# Controller.net
KiCad netlist of a schematic drawn in Altium Designer
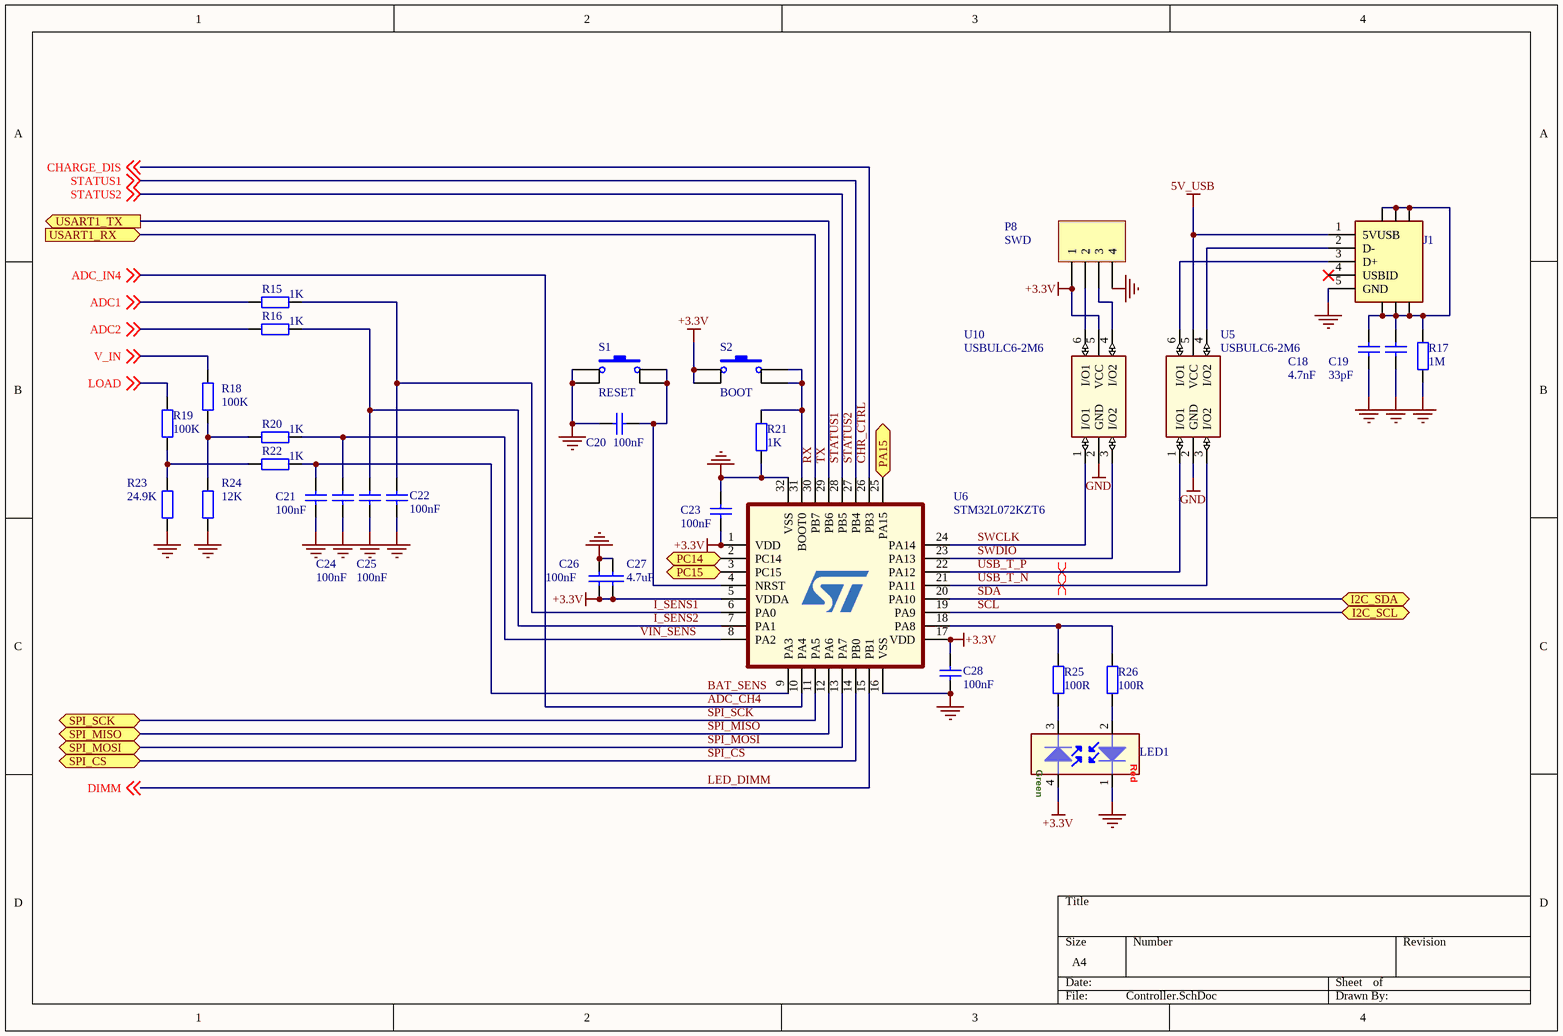
[diagram p0: Controller.SchDoc]

(export (version "E")
  (design (tool "Eeschema 10.0.6"))
  (components
    (comp (ref "C18")
      (value "4.7nF")
      (footprint "C0402")
      (description "Capacitor ceramic")
      (fields
        (field (name "MANUFACTURER") "Yageo")
        (field (name "MANUFACTURER PART NO.") "AC0402KRX7R9BB472")
      )
      (libsource (lib "Miscellaneous Devices") (part "Cap Semi"))
    )
    (comp (ref "C19")
      (value "33pF")
      (footprint "C0402")
      (description "Capacitor ceramic")
      (fields
        (field (name "MANUFACTURER") "Yageo")
        (field (name "MANUFACTURER PART NO.") "CC0402JRNPO9BN330")
      )
      (libsource (lib "Miscellaneous Devices") (part "Cap Semi"))
    )
    (comp (ref "C20")
      (value "100nF")
      (footprint "C0402")
      (description "Capacitor ceramic")
      (fields
        (field (name "MANUFACTURER") "TDK Corporation")
        (field (name "MANUFACTURER PART NO.") "CGA2B3X7R1V104K050BB")
      )
      (libsource (lib "Miscellaneous Devices") (part "Cap Semi"))
    )
    (comp (ref "C21")
      (value "100nF")
      (footprint "C0402")
      (description "Capacitor ceramic")
      (fields
        (field (name "MANUFACTURER") "TDK Corporation")
        (field (name "MANUFACTURER PART NO.") "CGA2B3X7R1V104K050BB")
      )
      (libsource (lib "Miscellaneous Devices") (part "Cap"))
    )
    (comp (ref "C22")
      (value "100nF")
      (footprint "C0402")
      (description "Capacitor ceramic")
      (fields
        (field (name "MANUFACTURER") "TDK Corporation")
        (field (name "MANUFACTURER PART NO.") "CGA2B3X7R1V104K050BB")
      )
      (libsource (lib "Miscellaneous Devices") (part "Cap"))
    )
    (comp (ref "C23")
      (value "100nF")
      (footprint "C0402")
      (description "Capacitor ceramic")
      (fields
        (field (name "MANUFACTURER") "TDK Corporation")
        (field (name "MANUFACTURER PART NO.") "CGA2B3X7R1V104K050BB")
      )
      (libsource (lib "Miscellaneous Devices") (part "Cap"))
    )
    (comp (ref "C24")
      (value "100nF")
      (footprint "C0402")
      (description "Capacitor ceramic")
      (fields
        (field (name "MANUFACTURER") "TDK Corporation")
        (field (name "MANUFACTURER PART NO.") "CGA2B3X7R1V104K050BB")
      )
      (libsource (lib "Miscellaneous Devices") (part "Cap"))
    )
    (comp (ref "C25")
      (value "100nF")
      (footprint "C0402")
      (description "Capacitor ceramic")
      (fields
        (field (name "MANUFACTURER") "TDK Corporation")
        (field (name "MANUFACTURER PART NO.") "CGA2B3X7R1V104K050BB")
      )
      (libsource (lib "Miscellaneous Devices") (part "Cap"))
    )
    (comp (ref "C26")
      (value "100nF")
      (footprint "C0402")
      (description "Capacitor ceramic")
      (fields
        (field (name "MANUFACTURER") "TDK Corporation")
        (field (name "MANUFACTURER PART NO.") "CGA2B3X7R1V104K050BB")
      )
      (libsource (lib "Miscellaneous Devices") (part "Cap"))
    )
    (comp (ref "C27")
      (value "4.7uF")
      (footprint "C0805")
      (description "Capacitor ceramic")
      (fields
        (field (name "MANUFACTURER") "Murata Electronics")
        (field (name "MANUFACTURER PART NO.") "GRM219R6YA475KA73D")
      )
      (libsource (lib "Miscellaneous Devices") (part "Cap Semi"))
    )
    (comp (ref "C28")
      (value "100nF")
      (footprint "C0402")
      (description "Capacitor ceramic")
      (fields
        (field (name "MANUFACTURER") "TDK Corporation")
        (field (name "MANUFACTURER PART NO.") "CGA2B3X7R1V104K050BB")
      )
      (libsource (lib "Miscellaneous Devices") (part "Cap"))
    )
    (comp (ref "J1")
      (value "CON-000116-01")
      (footprint "10118192-0001LF")
      (fields
        (field (name "MANUFACTURER") "Amphenol ICC (FCI)")
        (field (name "MANUFACTURER PART NO.") "10118192-0001LF")
      )
      (libsource (lib "MPPT_Charger_NB_IoT") (part "CON-000116-01"))
    )
    (comp (ref "LED1")
      (value "LED_BICOLOR")
      (footprint "PLCC-4")
      (fields
        (field (name "MANUFACTURER") "OSRAM Opto Semiconductors Inc.")
        (field (name "MANUFACTURER PART NO.") "LSG T67K-JL-1+HK-1")
      )
      (libsource (lib "LED_BiColor") (part "LED_BICOLOR"))
    )
    (comp (ref "P8")
      (value "SWD")
      (footprint "HDR1X4")
      (description "Header, 4-Pin")
      (fields
        (field (name "MANUFACTURER") "Samtec Inc.")
        (field (name "MANUFACTURER PART NO.") "SLW-104-01-G-S")
      )
      (libsource (lib "Miscellaneous Connectors") (part "Header 4"))
    )
    (comp (ref "R15")
      (value "1K")
      (footprint "R0402")
      (description "Resistor")
      (fields (field (name "MANUFACTURER") "Yageo") (field (name "MANUFACTURER PART NO.") "AC0402JR-071KL"))
      (libsource (lib "") (part "Res2_2"))
    )
    (comp (ref "R16")
      (value "1K")
      (footprint "R0402")
      (description "Resistor")
      (fields (field (name "MANUFACTURER") "Yageo") (field (name "MANUFACTURER PART NO.") "AC0402JR-071KL"))
      (libsource (lib "") (part "Res2_2"))
    )
    (comp (ref "R17")
      (value "1M")
      (footprint "R0402")
      (description "Resistor")
      (fields (field (name "MANUFACTURER") "Yageo") (field (name "MANUFACTURER PART NO.") "RC0402FR-071ML"))
      (libsource (lib "") (part "Res2_1"))
    )
    (comp (ref "R18")
      (value "100K")
      (footprint "R0402")
      (description "Resistor")
      (fields (field (name "MANUFACTURER") "Yageo") (field (name "MANUFACTURER PART NO.") "RC0402JR-07100KL"))
      (libsource (lib "") (part "Res2_1"))
    )
    (comp (ref "R19")
      (value "100K")
      (footprint "R0402")
      (description "Resistor")
      (fields (field (name "MANUFACTURER") "Yageo") (field (name "MANUFACTURER PART NO.") "RC0402JR-07100KL"))
      (libsource (lib "Miscellaneous Devices") (part "Res2"))
    )
    (comp (ref "R20")
      (value "1K")
      (footprint "R0402")
      (description "Resistor")
      (fields (field (name "MANUFACTURER") "Yageo") (field (name "MANUFACTURER PART NO.") "AC0402JR-071KL"))
      (libsource (lib "") (part "Res2_2"))
    )
    (comp (ref "R21")
      (value "1K")
      (footprint "R0402")
      (description "Resistor")
      (fields (field (name "MANUFACTURER") "Yageo") (field (name "MANUFACTURER PART NO.") "AC0402JR-071KL"))
      (libsource (lib "") (part "Res2_1"))
    )
    (comp (ref "R22")
      (value "1K")
      (footprint "R0402")
      (description "Resistor")
      (fields (field (name "MANUFACTURER") "Yageo") (field (name "MANUFACTURER PART NO.") "AC0402JR-071KL"))
      (libsource (lib "") (part "Res2_2"))
    )
    (comp (ref "R23")
      (value "24.9K")
      (footprint "R0402")
      (description "Resistor")
      (fields (field (name "MANUFACTURER") "Yageo") (field (name "MANUFACTURER PART NO.") "RC0402FR-0724K9L"))
      (libsource (lib "Miscellaneous Devices") (part "Res2"))
    )
    (comp (ref "R24")
      (value "12K")
      (footprint "R0402")
      (description "Resistor")
      (fields (field (name "MANUFACTURER") "Yageo") (field (name "MANUFACTURER PART NO.") "RC0402JR-0712KL"))
      (libsource (lib "") (part "Res2_1"))
    )
    (comp (ref "R25")
      (value "100R")
      (footprint "R0402")
      (description "Resistor")
      (fields (field (name "MANUFACTURER") "Yageo") (field (name "MANUFACTURER PART NO.") "SR0402JR-7W100RL"))
      (libsource (lib "Miscellaneous Devices") (part "Res2"))
    )
    (comp (ref "R26")
      (value "100R")
      (footprint "R0402")
      (description "Resistor")
      (fields (field (name "MANUFACTURER") "Yageo") (field (name "MANUFACTURER PART NO.") "SR0402JR-7W100RL"))
      (libsource (lib "Miscellaneous Devices") (part "Res2"))
    )
    (comp (ref "S1")
      (value "RESET")
      (footprint "EVQPUA")
      (description "Switch")
      (fields (field (name "MANUFACTURER") "Panasonic") (field (name "MANUFACTURER PART NO.") "EVQPUJ02K"))
      (libsource (lib "RUT_GE310_GNSS") (part "SW-PB"))
    )
    (comp (ref "S2")
      (value "BOOT")
      (footprint "EVQPUA")
      (description "Switch")
      (fields (field (name "MANUFACTURER") "Panasonic") (field (name "MANUFACTURER PART NO.") "EVQPUJ02K"))
      (libsource (lib "RUT_GE310_GNSS") (part "SW-PB"))
    )
    (comp (ref "U5")
      (value "USBULC6-2M6")
      (footprint "Micro_QFN_6L")
      (description "Ultra large bandwidth ESD protection")
      (fields (field (name "MANUFACTURER") "STMicroelectronics"))
      (libsource (lib "USBULC6-2M6") (part "USBULC6-2M6"))
    )
    (comp (ref "U6")
      (value "STM32L072KZT6")
      (footprint "LQFP32")
      (description "Ultra-low-power 32-bit MCU Arm®-based Cortex®-M0+")
      (fields (field (name "MANUFACTURER") "STMicroelectronics"))
      (libsource (lib "STM32L072KZT6") (part "STM32L072KZT6"))
    )
    (comp (ref "U10")
      (value "USBULC6-2M6")
      (footprint "Micro_QFN_6L")
      (description "Ultra large bandwidth ESD protection")
      (fields (field (name "MANUFACTURER") "STMicroelectronics"))
      (libsource (lib "USBULC6-2M6") (part "USBULC6-2M6"))
    )
  )
  (nets
    (net (code "1") (name "+3.3V") (class "Default")
      (node (ref "C23") (pin "2") (pinfunction "2_2") (pintype "passive"))
      (node (ref "C26") (pin "2") (pinfunction "2_2") (pintype "passive"))
      (node (ref "C27") (pin "1") (pinfunction "1_1") (pintype "passive"))
      (node (ref "C28") (pin "1") (pinfunction "1_1") (pintype "passive"))
      (node (ref "LED1") (pin "4") (pinfunction "4_4") (pintype "passive"))
      (node (ref "P8") (pin "1") (pinfunction "1_1") (pintype "passive"))
      (node (ref "S2") (pin "1") (pinfunction "1_1") (pintype "passive"))
      (node (ref "S2") (pin "3") (pinfunction "3_3") (pintype "passive"))
      (node (ref "U10") (pin "5") (pinfunction "VCC_5") (pintype "power_in"))
      (node (ref "U6") (pin "1") (pinfunction "VDD_1") (pintype "passive"))
      (node (ref "U6") (pin "17") (pinfunction "VDD_17") (pintype "passive"))
      (node (ref "U6") (pin "5") (pinfunction "VDDA_5") (pintype "passive"))
    )
    (net (code "2") (name "/BAT_SENS") (class "Default")
      (node (ref "C21") (pin "1") (pinfunction "1_1") (pintype "passive"))
      (node (ref "R22") (pin "2") (pinfunction "2_2") (pintype "passive"))
      (node (ref "U6") (pin "9") (pinfunction "PA3_9") (pintype "passive"))
    )
    (net (code "3") (name "/I_SENS1") (class "Default")
      (node (ref "C22") (pin "1") (pinfunction "1_1") (pintype "passive"))
      (node (ref "R15") (pin "2") (pinfunction "2_2") (pintype "passive"))
      (node (ref "U6") (pin "6") (pinfunction "PA0_6") (pintype "passive"))
    )
    (net (code "4") (name "/I_SENS2") (class "Default")
      (node (ref "C25") (pin "1") (pinfunction "1_1") (pintype "passive"))
      (node (ref "R16") (pin "2") (pinfunction "2_2") (pintype "passive"))
      (node (ref "U6") (pin "7") (pinfunction "PA1_7") (pintype "passive"))
    )
    (net (code "5") (name "/PA15") (class "Default")
      (node (ref "U6") (pin "25") (pinfunction "PA15_25") (pintype "passive"))
    )
    (net (code "6") (name "/PC14") (class "Default")
      (node (ref "U6") (pin "2") (pinfunction "PC14_2") (pintype "passive"))
    )
    (net (code "7") (name "/PC15") (class "Default")
      (node (ref "U6") (pin "3") (pinfunction "PC15_3") (pintype "passive"))
    )
    (net (code "8") (name "/RX") (class "Default")
      (node (ref "U6") (pin "30") (pinfunction "PB7_30") (pintype "passive"))
    )
    (net (code "9") (name "/SCL") (class "Default")
      (node (ref "U6") (pin "19") (pinfunction "PA9_19") (pintype "passive"))
    )
    (net (code "10") (name "/SDA") (class "Default")
      (node (ref "U6") (pin "20") (pinfunction "PA10_20") (pintype "passive"))
    )
    (net (code "11") (name "/SPI_CS") (class "Default")
      (node (ref "U6") (pin "14") (pinfunction "PB0_14") (pintype "passive"))
    )
    (net (code "12") (name "/SPI_MISO") (class "Default")
      (node (ref "U6") (pin "12") (pinfunction "PA6_12") (pintype "passive"))
    )
    (net (code "13") (name "/SPI_MOSI") (class "Default")
      (node (ref "U6") (pin "13") (pinfunction "PA7_13") (pintype "passive"))
    )
    (net (code "14") (name "/SPI_SCK") (class "Default")
      (node (ref "U6") (pin "11") (pinfunction "PA5_11") (pintype "passive"))
    )
    (net (code "15") (name "/SWCLK") (class "Default")
      (node (ref "U10") (pin "1") (pinfunction "I/O1_1") (pintype "bidirectional"))
      (node (ref "U6") (pin "24") (pinfunction "PA14_24") (pintype "passive"))
    )
    (net (code "16") (name "/SWDIO") (class "Default")
      (node (ref "U10") (pin "3") (pinfunction "I/O2_3") (pintype "bidirectional"))
      (node (ref "U6") (pin "23") (pinfunction "PA13_23") (pintype "passive"))
    )
    (net (code "17") (name "/TX") (class "Default")
      (node (ref "U6") (pin "29") (pinfunction "PB6_29") (pintype "passive"))
    )
    (net (code "18") (name "/USB_T_N") (class "Default")
      (node (ref "U5") (pin "3") (pinfunction "I/O2_3") (pintype "bidirectional"))
      (node (ref "U6") (pin "21") (pinfunction "PA11_21") (pintype "passive"))
    )
    (net (code "19") (name "/USB_T_P") (class "Default")
      (node (ref "U5") (pin "1") (pinfunction "I/O1_1") (pintype "bidirectional"))
      (node (ref "U6") (pin "22") (pinfunction "PA12_22") (pintype "passive"))
    )
    (net (code "20") (name "/VIN_SENS") (class "Default")
      (node (ref "C24") (pin "1") (pinfunction "1_1") (pintype "passive"))
      (node (ref "R20") (pin "2") (pinfunction "2_2") (pintype "passive"))
      (node (ref "U6") (pin "8") (pinfunction "PA2_8") (pintype "passive"))
    )
    (net (code "21") (name "5V_USB") (class "Default")
      (node (ref "J1") (pin "1") (pinfunction "5VUSB_1") (pintype "passive"))
      (node (ref "U5") (pin "5") (pinfunction "VCC_5") (pintype "power_in"))
    )
    (net (code "22") (name "ADC1") (class "Default")
      (node (ref "R15") (pin "1") (pinfunction "1_1") (pintype "passive"))
    )
    (net (code "23") (name "ADC2") (class "Default")
      (node (ref "R16") (pin "1") (pinfunction "1_1") (pintype "passive"))
    )
    (net (code "24") (name "ADC_IN4") (class "Default")
      (node (ref "U6") (pin "10") (pinfunction "PA4_10") (pintype "passive"))
    )
    (net (code "25") (name "CHARGE_DIS") (class "Default")
      (node (ref "U6") (pin "26") (pinfunction "PB3_26") (pintype "passive"))
    )
    (net (code "26") (name "DIMM") (class "Default")
      (node (ref "U6") (pin "15") (pinfunction "PB1_15") (pintype "passive"))
    )
    (net (code "27") (name "GND") (class "Default")
      (node (ref "C18") (pin "1") (pinfunction "1_1") (pintype "passive"))
      (node (ref "C19") (pin "1") (pinfunction "1_1") (pintype "passive"))
      (node (ref "C20") (pin "2") (pinfunction "2_2") (pintype "passive"))
      (node (ref "C21") (pin "2") (pinfunction "2_2") (pintype "passive"))
      (node (ref "C22") (pin "2") (pinfunction "2_2") (pintype "passive"))
      (node (ref "C23") (pin "1") (pinfunction "1_1") (pintype "passive"))
      (node (ref "C24") (pin "2") (pinfunction "2_2") (pintype "passive"))
      (node (ref "C25") (pin "2") (pinfunction "2_2") (pintype "passive"))
      (node (ref "C26") (pin "1") (pinfunction "1_1") (pintype "passive"))
      (node (ref "C27") (pin "2") (pinfunction "2_2") (pintype "passive"))
      (node (ref "C28") (pin "2") (pinfunction "2_2") (pintype "passive"))
      (node (ref "J1") (pin "5") (pinfunction "GND_5") (pintype "passive"))
      (node (ref "LED1") (pin "1") (pinfunction "1_1") (pintype "passive"))
      (node (ref "P8") (pin "4") (pinfunction "4_4") (pintype "passive"))
      (node (ref "R17") (pin "1") (pinfunction "1_1") (pintype "passive"))
      (node (ref "R21") (pin "1") (pinfunction "1_1") (pintype "passive"))
      (node (ref "R23") (pin "2") (pinfunction "2_2") (pintype "passive"))
      (node (ref "R24") (pin "1") (pinfunction "1_1") (pintype "passive"))
      (node (ref "S1") (pin "1") (pinfunction "1_1") (pintype "passive"))
      (node (ref "S1") (pin "3") (pinfunction "3_3") (pintype "passive"))
      (node (ref "U10") (pin "2") (pinfunction "GND_2") (pintype "power_in"))
      (node (ref "U5") (pin "2") (pinfunction "GND_2") (pintype "power_in"))
      (node (ref "U6") (pin "16") (pinfunction "VSS_16") (pintype "passive"))
      (node (ref "U6") (pin "32") (pinfunction "VSS_32") (pintype "passive"))
    )
    (net (code "28") (name "LOAD") (class "Default")
      (node (ref "R19") (pin "1") (pinfunction "1_1") (pintype "passive"))
    )
    (net (code "29") (name "Net-(C18-Pad2)") (class "Default")
      (node (ref "C18") (pin "2") (pinfunction "2_2") (pintype "passive"))
      (node (ref "C19") (pin "2") (pinfunction "2_2") (pintype "passive"))
      (node (ref "J1") (pin "10") (pinfunction "10_10") (pintype "passive"))
      (node (ref "J1") (pin "11") (pinfunction "11_11") (pintype "passive"))
      (node (ref "J1") (pin "6") (pinfunction "6_6") (pintype "passive"))
      (node (ref "J1") (pin "7") (pinfunction "7_7") (pintype "passive"))
      (node (ref "J1") (pin "8") (pinfunction "8_8") (pintype "passive"))
      (node (ref "J1") (pin "9") (pinfunction "9_9") (pintype "passive"))
      (node (ref "R17") (pin "2") (pinfunction "2_2") (pintype "passive"))
    )
    (net (code "30") (name "Net-(J1-D+)") (class "Default")
      (node (ref "J1") (pin "3") (pinfunction "D+_3") (pintype "passive"))
      (node (ref "U5") (pin "6") (pinfunction "I/O1_6") (pintype "bidirectional"))
    )
    (net (code "31") (name "Net-(J1-D-)") (class "Default")
      (node (ref "J1") (pin "2") (pinfunction "D-_2") (pintype "passive"))
      (node (ref "U5") (pin "4") (pinfunction "I/O2_4") (pintype "bidirectional"))
    )
    (net (code "32") (name "Net-(LED1-Pad2)") (class "Default")
      (node (ref "LED1") (pin "2") (pinfunction "2_2") (pintype "passive"))
      (node (ref "R26") (pin "2") (pinfunction "2_2") (pintype "passive"))
    )
    (net (code "33") (name "Net-(LED1-Pad3)") (class "Default")
      (node (ref "LED1") (pin "3") (pinfunction "3_3") (pintype "passive"))
      (node (ref "R25") (pin "2") (pinfunction "2_2") (pintype "passive"))
    )
    (net (code "34") (name "Net-(P8-Pad2)") (class "Default")
      (node (ref "P8") (pin "2") (pinfunction "2_2") (pintype "passive"))
      (node (ref "U10") (pin "6") (pinfunction "I/O1_6") (pintype "bidirectional"))
    )
    (net (code "35") (name "Net-(P8-Pad3)") (class "Default")
      (node (ref "P8") (pin "3") (pinfunction "3_3") (pintype "passive"))
      (node (ref "U10") (pin "4") (pinfunction "I/O2_4") (pintype "bidirectional"))
    )
    (net (code "36") (name "Net-(R18-Pad1)") (class "Default")
      (node (ref "R18") (pin "1") (pinfunction "1_1") (pintype "passive"))
      (node (ref "R20") (pin "1") (pinfunction "1_1") (pintype "passive"))
      (node (ref "R24") (pin "2") (pinfunction "2_2") (pintype "passive"))
    )
    (net (code "37") (name "Net-(R19-Pad2)") (class "Default")
      (node (ref "R19") (pin "2") (pinfunction "2_2") (pintype "passive"))
      (node (ref "R22") (pin "1") (pinfunction "1_1") (pintype "passive"))
      (node (ref "R23") (pin "1") (pinfunction "1_1") (pintype "passive"))
    )
    (net (code "38") (name "Net-(U6-BOOT0)") (class "Default")
      (node (ref "R21") (pin "2") (pinfunction "2_2") (pintype "passive"))
      (node (ref "S2") (pin "2") (pinfunction "2_2") (pintype "passive"))
      (node (ref "S2") (pin "4") (pinfunction "4_4") (pintype "passive"))
      (node (ref "U6") (pin "31") (pinfunction "BOOT0_31") (pintype "passive"))
    )
    (net (code "39") (name "Net-(U6-NRST)") (class "Default")
      (node (ref "C20") (pin "1") (pinfunction "1_1") (pintype "passive"))
      (node (ref "S1") (pin "2") (pinfunction "2_2") (pintype "passive"))
      (node (ref "S1") (pin "4") (pinfunction "4_4") (pintype "passive"))
      (node (ref "U6") (pin "4") (pinfunction "NRST_4") (pintype "passive"))
    )
    (net (code "40") (name "Net-(U6-PA8)") (class "Default")
      (node (ref "R25") (pin "1") (pinfunction "1_1") (pintype "passive"))
      (node (ref "R26") (pin "1") (pinfunction "1_1") (pintype "passive"))
      (node (ref "U6") (pin "18") (pinfunction "PA8_18") (pintype "passive"))
    )
    (net (code "41") (name "STATUS1") (class "Default")
      (node (ref "U6") (pin "27") (pinfunction "PB4_27") (pintype "passive"))
      (node (ref "U6") (pin "28") (pinfunction "PB5_28") (pintype "passive"))
    )
    (net (code "42") (name "V_IN") (class "Default")
      (node (ref "R18") (pin "2") (pinfunction "2_2") (pintype "passive"))
    )
    (net (code "43") (name "unconnected-(J1-USBID-Pad4)") (class "Default")
      (node (ref "J1") (pin "4") (pinfunction "USBID_4") (pintype "passive+no_connect"))
    )
  )
)
